# Sheet3.net
KiCad netlist of a schematic drawn in Altium Designer
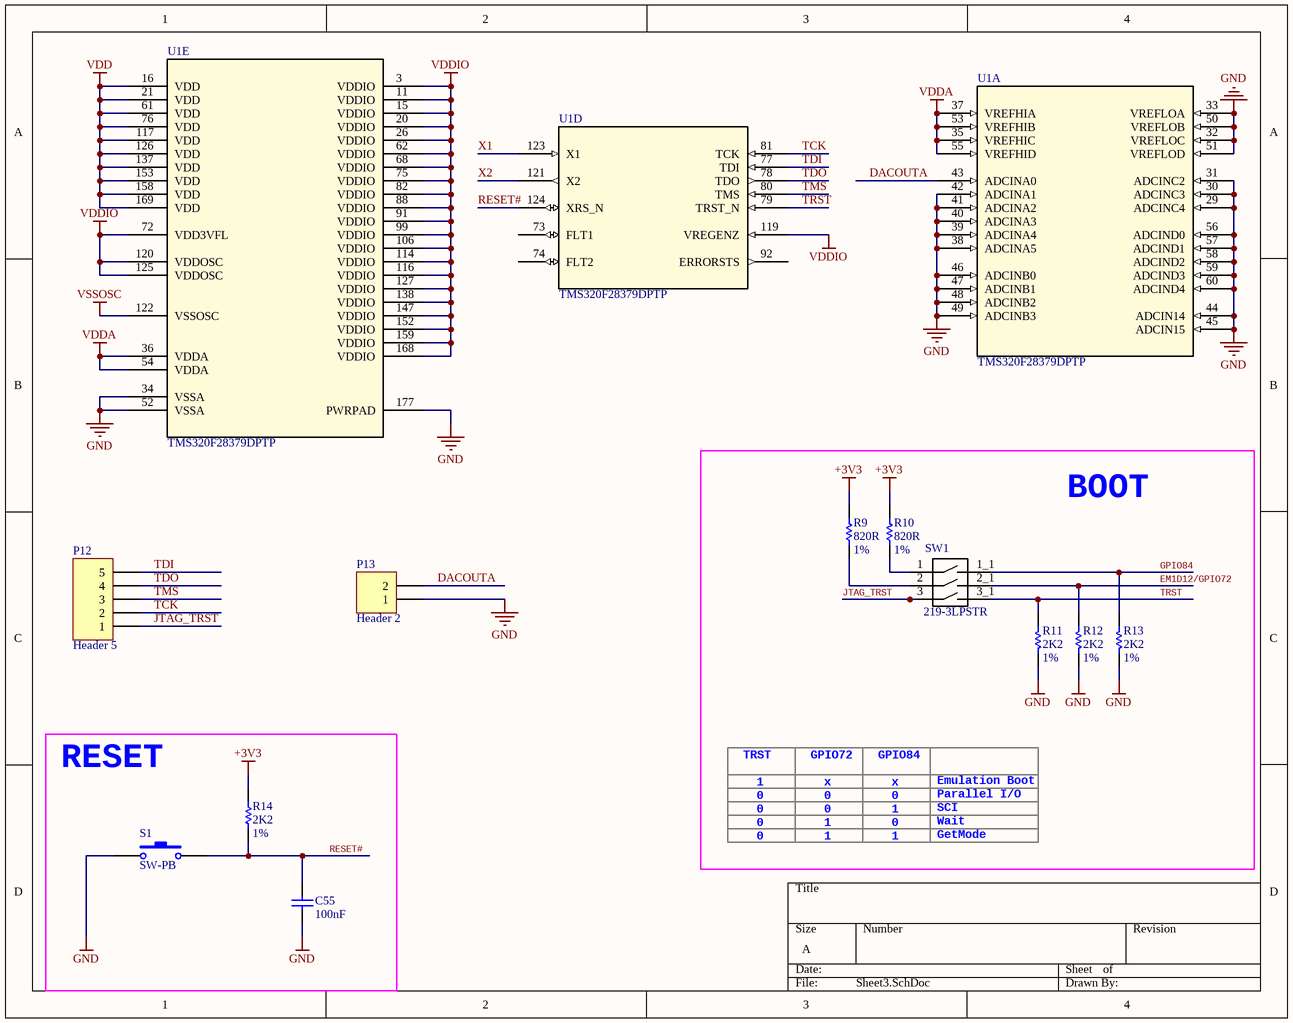
[diagram p0: Sheet3.SchDoc]

(export (version "E")
  (design (tool "Eeschema 10.0.6"))
  (components
    (comp (ref "C55")
      (value "100nF")
      (footprint "C0805")
      (description "CAP,100NF(0.1uf),+/-10%,X5R,10V,SMD0402")
      (fields
        (field (name "MANUFACTURER") "MURATA")
        (field (name "MANUFACTURER PART NUMBER") "GRM155R61A104KA01D")
      )
      (libsource (lib "Embest") (part "C"))
    )
    (comp (ref "P12")
      (value "Header 5")
      (footprint "HDR1X5")
      (description "Header, 5-Pin")
      (fields (field (name "PUBLISHER") "Altium Limited"))
      (libsource (lib "Miscellaneous Connectors") (part "Header 5"))
    )
    (comp (ref "P13")
      (value "Header 2")
      (footprint "HDR1X2")
      (description "Header, 2-Pin")
      (fields (field (name "PUBLISHER") "Altium Limited"))
      (libsource (lib "Miscellaneous Connectors") (part "Header 2"))
    )
    (comp (ref "R9")
      (value "820R")
      (footprint "6-0805_L")
      (description "RES,820R,+/-1%,1/16W,SMD0402")
      (fields
        (field (name "RATING") "1%")
        (field (name "MANUFACTURER") "YAGEO")
        (field (name "MANUFACTURER PART NUMBER") "RC0402FR-07820RL")
      )
      (libsource (lib "Embest") (part "R"))
    )
    (comp (ref "R10")
      (value "820R")
      (footprint "6-0805_L")
      (description "RES,820R,+/-1%,1/16W,SMD0402")
      (fields
        (field (name "RATING") "1%")
        (field (name "MANUFACTURER") "YAGEO")
        (field (name "MANUFACTURER PART NUMBER") "RC0402FR-07820RL")
      )
      (libsource (lib "Embest") (part "R"))
    )
    (comp (ref "R11")
      (value "2K2")
      (footprint "6-0805_L")
      (description "RES,2K2,+/-1%,1/16W,SMD0402")
      (fields
        (field (name "RATING") "1%")
        (field (name "MANUFACTURER") "YAGEO")
        (field (name "MANUFACTURER PART NUMBER") "RC0402FR-072K2L")
      )
      (libsource (lib "Embest") (part "R"))
    )
    (comp (ref "R12")
      (value "2K2")
      (footprint "6-0805_L")
      (description "RES,2K2,+/-1%,1/16W,SMD0402")
      (fields
        (field (name "RATING") "1%")
        (field (name "MANUFACTURER") "YAGEO")
        (field (name "MANUFACTURER PART NUMBER") "RC0402FR-072K2L")
      )
      (libsource (lib "Embest") (part "R"))
    )
    (comp (ref "R13")
      (value "2K2")
      (footprint "6-0805_L")
      (description "RES,2K2,+/-1%,1/16W,SMD0402")
      (fields
        (field (name "RATING") "1%")
        (field (name "MANUFACTURER") "YAGEO")
        (field (name "MANUFACTURER PART NUMBER") "RC0402FR-072K2L")
      )
      (libsource (lib "Embest") (part "R"))
    )
    (comp (ref "R14")
      (value "2K2")
      (footprint "6-0805_L")
      (description "RES,2K2,+/-1%,1/16W,SMD0402")
      (fields
        (field (name "RATING") "1%")
        (field (name "MANUFACTURER") "YAGEO")
        (field (name "MANUFACTURER PART NUMBER") "RC0402FR-072K2L")
      )
      (libsource (lib "Embest") (part "R"))
    )
    (comp (ref "S1")
      (value "SW-PB")
      (footprint "SW PB")
      (description "DIGIKEY SW400-ND")
      (fields (field (name "PUBLISHER") "Altium Limited"))
      (libsource (lib "ECE LIB new") (part "SW-PB"))
    )
    (comp (ref "SW1")
      (value "219-3LPSTR")
      (footprint "219-3LPSTR:3Switch*SW_219-3LPSTR3W219-3LPSTR(Primary)")
      (description "Dip Switch SPST 3 Position Surface Mount Slide _Standard_ Actuator 100mA 20VDC")
      (fields (field (name "DIGI-KEY_PART_NUMBER") "CT3115CT-ND") (field (name "MF") "CTS Electrocomponents"))
      (libsource (lib "219-3LPSTR") (part "219-3LPSTR"))
    )
    (comp (ref "U1")
      (value "TMS320F28379DPTP")
      (footprint "PTP0176F_L")
      (description "Imported")
      (fields
        (field (name "PARTNUMBER") "TMS320F28379DPTPS")
        (field (name "MANUFACTURER") "Texas Instruments")
      )
      (libsource (lib "TMS320F28379DPTPT") (part "TMS320F28379DPTP"))
    )
  )
  (nets
    (net (code "1") (name "+3V3") (class "Default")
      (node (ref "R10") (pin "2") (pinfunction "2_2") (pintype "passive"))
      (node (ref "R14") (pin "2") (pinfunction "2_2") (pintype "passive"))
      (node (ref "R9") (pin "2") (pinfunction "2_2") (pintype "passive"))
    )
    (net (code "2") (name "/DACOUTA") (class "Default")
      (node (ref "P13") (pin "2") (pinfunction "2_2") (pintype "passive"))
      (node (ref "U1") (pin "43") (pinfunction "ADCINA0_43") (pintype "input"))
    )
    (net (code "3") (name "/EM1D12{slash}GPIO72") (class "Default")
      (node (ref "R12") (pin "2") (pinfunction "2_2") (pintype "passive"))
      (node (ref "SW1") (pin "2_1") (pinfunction "2_1_2_1") (pintype "passive"))
    )
    (net (code "4") (name "/GPIO84") (class "Default")
      (node (ref "R13") (pin "2") (pinfunction "2_2") (pintype "passive"))
      (node (ref "SW1") (pin "1_1") (pinfunction "1_1_1_1") (pintype "passive"))
    )
    (net (code "5") (name "/JTAG_TRST") (class "Default")
      (node (ref "P12") (pin "1") (pinfunction "1_1") (pintype "passive"))
      (node (ref "SW1") (pin "3") (pinfunction "3_3") (pintype "passive"))
    )
    (net (code "6") (name "/RESET#") (class "Default")
      (node (ref "C55") (pin "1") (pinfunction "1_1") (pintype "passive"))
      (node (ref "R14") (pin "1") (pinfunction "1_1") (pintype "passive"))
      (node (ref "S1") (pin "2") (pinfunction "2_2") (pintype "passive"))
      (node (ref "U1") (pin "124") (pinfunction "XRS_N_124") (pintype "bidirectional"))
    )
    (net (code "7") (name "/TCK") (class "Default")
      (node (ref "P12") (pin "2") (pinfunction "2_2") (pintype "passive"))
      (node (ref "U1") (pin "81") (pinfunction "TCK_81") (pintype "input"))
    )
    (net (code "8") (name "/TDI") (class "Default")
      (node (ref "P12") (pin "5") (pinfunction "5_5") (pintype "passive"))
      (node (ref "U1") (pin "77") (pinfunction "TDI_77") (pintype "input"))
    )
    (net (code "9") (name "/TDO") (class "Default")
      (node (ref "P12") (pin "4") (pinfunction "4_4") (pintype "passive"))
      (node (ref "U1") (pin "78") (pinfunction "TDO_78") (pintype "output"))
    )
    (net (code "10") (name "/TMS") (class "Default")
      (node (ref "P12") (pin "3") (pinfunction "3_3") (pintype "passive"))
      (node (ref "U1") (pin "80") (pinfunction "TMS_80") (pintype "input"))
    )
    (net (code "11") (name "/TRST") (class "Default")
      (node (ref "R11") (pin "2") (pinfunction "2_2") (pintype "passive"))
      (node (ref "SW1") (pin "3_1") (pinfunction "3_1_3_1") (pintype "passive"))
      (node (ref "U1") (pin "79") (pinfunction "TRST_N_79") (pintype "input"))
    )
    (net (code "12") (name "/X1") (class "Default")
      (node (ref "U1") (pin "123") (pinfunction "X1_123") (pintype "input"))
    )
    (net (code "13") (name "/X2") (class "Default")
      (node (ref "U1") (pin "121") (pinfunction "X2_121") (pintype "output"))
    )
    (net (code "14") (name "GND") (class "Default")
      (node (ref "C55") (pin "2") (pinfunction "2_2") (pintype "passive"))
      (node (ref "P13") (pin "1") (pinfunction "1_1") (pintype "passive"))
      (node (ref "R11") (pin "1") (pinfunction "1_1") (pintype "passive"))
      (node (ref "R12") (pin "1") (pinfunction "1_1") (pintype "passive"))
      (node (ref "R13") (pin "1") (pinfunction "1_1") (pintype "passive"))
      (node (ref "S1") (pin "1") (pinfunction "1_1") (pintype "passive"))
      (node (ref "U1") (pin "177") (pinfunction "PWRPAD_177") (pintype "power_in"))
      (node (ref "U1") (pin "29") (pinfunction "ADCINC4_29") (pintype "input"))
      (node (ref "U1") (pin "30") (pinfunction "ADCINC3_30") (pintype "input"))
      (node (ref "U1") (pin "31") (pinfunction "ADCINC2_31") (pintype "input"))
      (node (ref "U1") (pin "32") (pinfunction "VREFLOC_32") (pintype "input"))
      (node (ref "U1") (pin "33") (pinfunction "VREFLOA_33") (pintype "input"))
      (node (ref "U1") (pin "34") (pinfunction "VSSA_34") (pintype "power_in"))
      (node (ref "U1") (pin "38") (pinfunction "ADCINA5_38") (pintype "input"))
      (node (ref "U1") (pin "39") (pinfunction "ADCINA4_39") (pintype "input"))
      (node (ref "U1") (pin "40") (pinfunction "ADCINA3_40") (pintype "input"))
      (node (ref "U1") (pin "41") (pinfunction "ADCINA2_41") (pintype "input"))
      (node (ref "U1") (pin "42") (pinfunction "ADCINA1_42") (pintype "input"))
      (node (ref "U1") (pin "44") (pinfunction "ADCIN14_44") (pintype "input"))
      (node (ref "U1") (pin "45") (pinfunction "ADCIN15_45") (pintype "input"))
      (node (ref "U1") (pin "46") (pinfunction "ADCINB0_46") (pintype "input"))
      (node (ref "U1") (pin "47") (pinfunction "ADCINB1_47") (pintype "input"))
      (node (ref "U1") (pin "48") (pinfunction "ADCINB2_48") (pintype "input"))
      (node (ref "U1") (pin "49") (pinfunction "ADCINB3_49") (pintype "input"))
      (node (ref "U1") (pin "50") (pinfunction "VREFLOB_50") (pintype "input"))
      (node (ref "U1") (pin "51") (pinfunction "VREFLOD_51") (pintype "input"))
      (node (ref "U1") (pin "52") (pinfunction "VSSA_52") (pintype "power_in"))
      (node (ref "U1") (pin "56") (pinfunction "ADCIND0_56") (pintype "input"))
      (node (ref "U1") (pin "57") (pinfunction "ADCIND1_57") (pintype "input"))
      (node (ref "U1") (pin "58") (pinfunction "ADCIND2_58") (pintype "input"))
      (node (ref "U1") (pin "59") (pinfunction "ADCIND3_59") (pintype "input"))
      (node (ref "U1") (pin "60") (pinfunction "ADCIND4_60") (pintype "input"))
    )
    (net (code "15") (name "Net-(R9-Pad1)") (class "Default")
      (node (ref "R9") (pin "1") (pinfunction "1_1") (pintype "passive"))
      (node (ref "SW1") (pin "2") (pinfunction "2_2") (pintype "passive"))
    )
    (net (code "16") (name "Net-(R10-Pad1)") (class "Default")
      (node (ref "R10") (pin "1") (pinfunction "1_1") (pintype "passive"))
      (node (ref "SW1") (pin "1") (pinfunction "1_1") (pintype "passive"))
    )
    (net (code "17") (name "VDD") (class "Default")
      (node (ref "U1") (pin "117") (pinfunction "VDD_117") (pintype "power_in"))
      (node (ref "U1") (pin "126") (pinfunction "VDD_126") (pintype "power_in"))
      (node (ref "U1") (pin "137") (pinfunction "VDD_137") (pintype "power_in"))
      (node (ref "U1") (pin "153") (pinfunction "VDD_153") (pintype "power_in"))
      (node (ref "U1") (pin "158") (pinfunction "VDD_158") (pintype "power_in"))
      (node (ref "U1") (pin "16") (pinfunction "VDD_16") (pintype "power_in"))
      (node (ref "U1") (pin "169") (pinfunction "VDD_169") (pintype "power_in"))
      (node (ref "U1") (pin "21") (pinfunction "VDD_21") (pintype "power_in"))
      (node (ref "U1") (pin "61") (pinfunction "VDD_61") (pintype "power_in"))
      (node (ref "U1") (pin "76") (pinfunction "VDD_76") (pintype "power_in"))
    )
    (net (code "18") (name "VDDA") (class "Default")
      (node (ref "U1") (pin "35") (pinfunction "VREFHIC_35") (pintype "input"))
      (node (ref "U1") (pin "36") (pinfunction "VDDA_36") (pintype "power_in"))
      (node (ref "U1") (pin "37") (pinfunction "VREFHIA_37") (pintype "input"))
      (node (ref "U1") (pin "53") (pinfunction "VREFHIB_53") (pintype "input"))
      (node (ref "U1") (pin "54") (pinfunction "VDDA_54") (pintype "power_in"))
      (node (ref "U1") (pin "55") (pinfunction "VREFHID_55") (pintype "input"))
    )
    (net (code "19") (name "VDDIO") (class "Default")
      (node (ref "U1") (pin "106") (pinfunction "VDDIO_106") (pintype "power_in"))
      (node (ref "U1") (pin "11") (pinfunction "VDDIO_11") (pintype "power_in"))
      (node (ref "U1") (pin "114") (pinfunction "VDDIO_114") (pintype "power_in"))
      (node (ref "U1") (pin "116") (pinfunction "VDDIO_116") (pintype "power_in"))
      (node (ref "U1") (pin "119") (pinfunction "VREGENZ_119") (pintype "input"))
      (node (ref "U1") (pin "120") (pinfunction "VDDOSC_120") (pintype "power_in"))
      (node (ref "U1") (pin "125") (pinfunction "VDDOSC_125") (pintype "power_in"))
      (node (ref "U1") (pin "127") (pinfunction "VDDIO_127") (pintype "power_in"))
      (node (ref "U1") (pin "138") (pinfunction "VDDIO_138") (pintype "power_in"))
      (node (ref "U1") (pin "147") (pinfunction "VDDIO_147") (pintype "power_in"))
      (node (ref "U1") (pin "15") (pinfunction "VDDIO_15") (pintype "power_in"))
      (node (ref "U1") (pin "152") (pinfunction "VDDIO_152") (pintype "power_in"))
      (node (ref "U1") (pin "159") (pinfunction "VDDIO_159") (pintype "power_in"))
      (node (ref "U1") (pin "168") (pinfunction "VDDIO_168") (pintype "power_in"))
      (node (ref "U1") (pin "20") (pinfunction "VDDIO_20") (pintype "power_in"))
      (node (ref "U1") (pin "26") (pinfunction "VDDIO_26") (pintype "power_in"))
      (node (ref "U1") (pin "3") (pinfunction "VDDIO_3") (pintype "power_in"))
      (node (ref "U1") (pin "62") (pinfunction "VDDIO_62") (pintype "power_in"))
      (node (ref "U1") (pin "68") (pinfunction "VDDIO_68") (pintype "power_in"))
      (node (ref "U1") (pin "72") (pinfunction "VDD3VFL_72") (pintype "power_in"))
      (node (ref "U1") (pin "75") (pinfunction "VDDIO_75") (pintype "power_in"))
      (node (ref "U1") (pin "82") (pinfunction "VDDIO_82") (pintype "power_in"))
      (node (ref "U1") (pin "88") (pinfunction "VDDIO_88") (pintype "power_in"))
      (node (ref "U1") (pin "91") (pinfunction "VDDIO_91") (pintype "power_in"))
      (node (ref "U1") (pin "99") (pinfunction "VDDIO_99") (pintype "power_in"))
    )
    (net (code "20") (name "VSSOSC") (class "Default")
      (node (ref "U1") (pin "122") (pinfunction "VSSOSC_122") (pintype "power_in"))
    )
    (net (code "21") (name "unconnected-(U1D-ERRORSTS-Pad92)") (class "Default")
      (node (ref "U1") (pin "92") (pinfunction "ERRORSTS_92") (pintype "output"))
    )
    (net (code "22") (name "unconnected-(U1D-FLT1-Pad73)") (class "Default")
      (node (ref "U1") (pin "73") (pinfunction "FLT1_73") (pintype "bidirectional"))
    )
    (net (code "23") (name "unconnected-(U1D-FLT2-Pad74)") (class "Default")
      (node (ref "U1") (pin "74") (pinfunction "FLT2_74") (pintype "bidirectional"))
    )
  )
)
